# MTB-v1_2_0.net
KiCad netlist of a schematic drawn in EAGLE
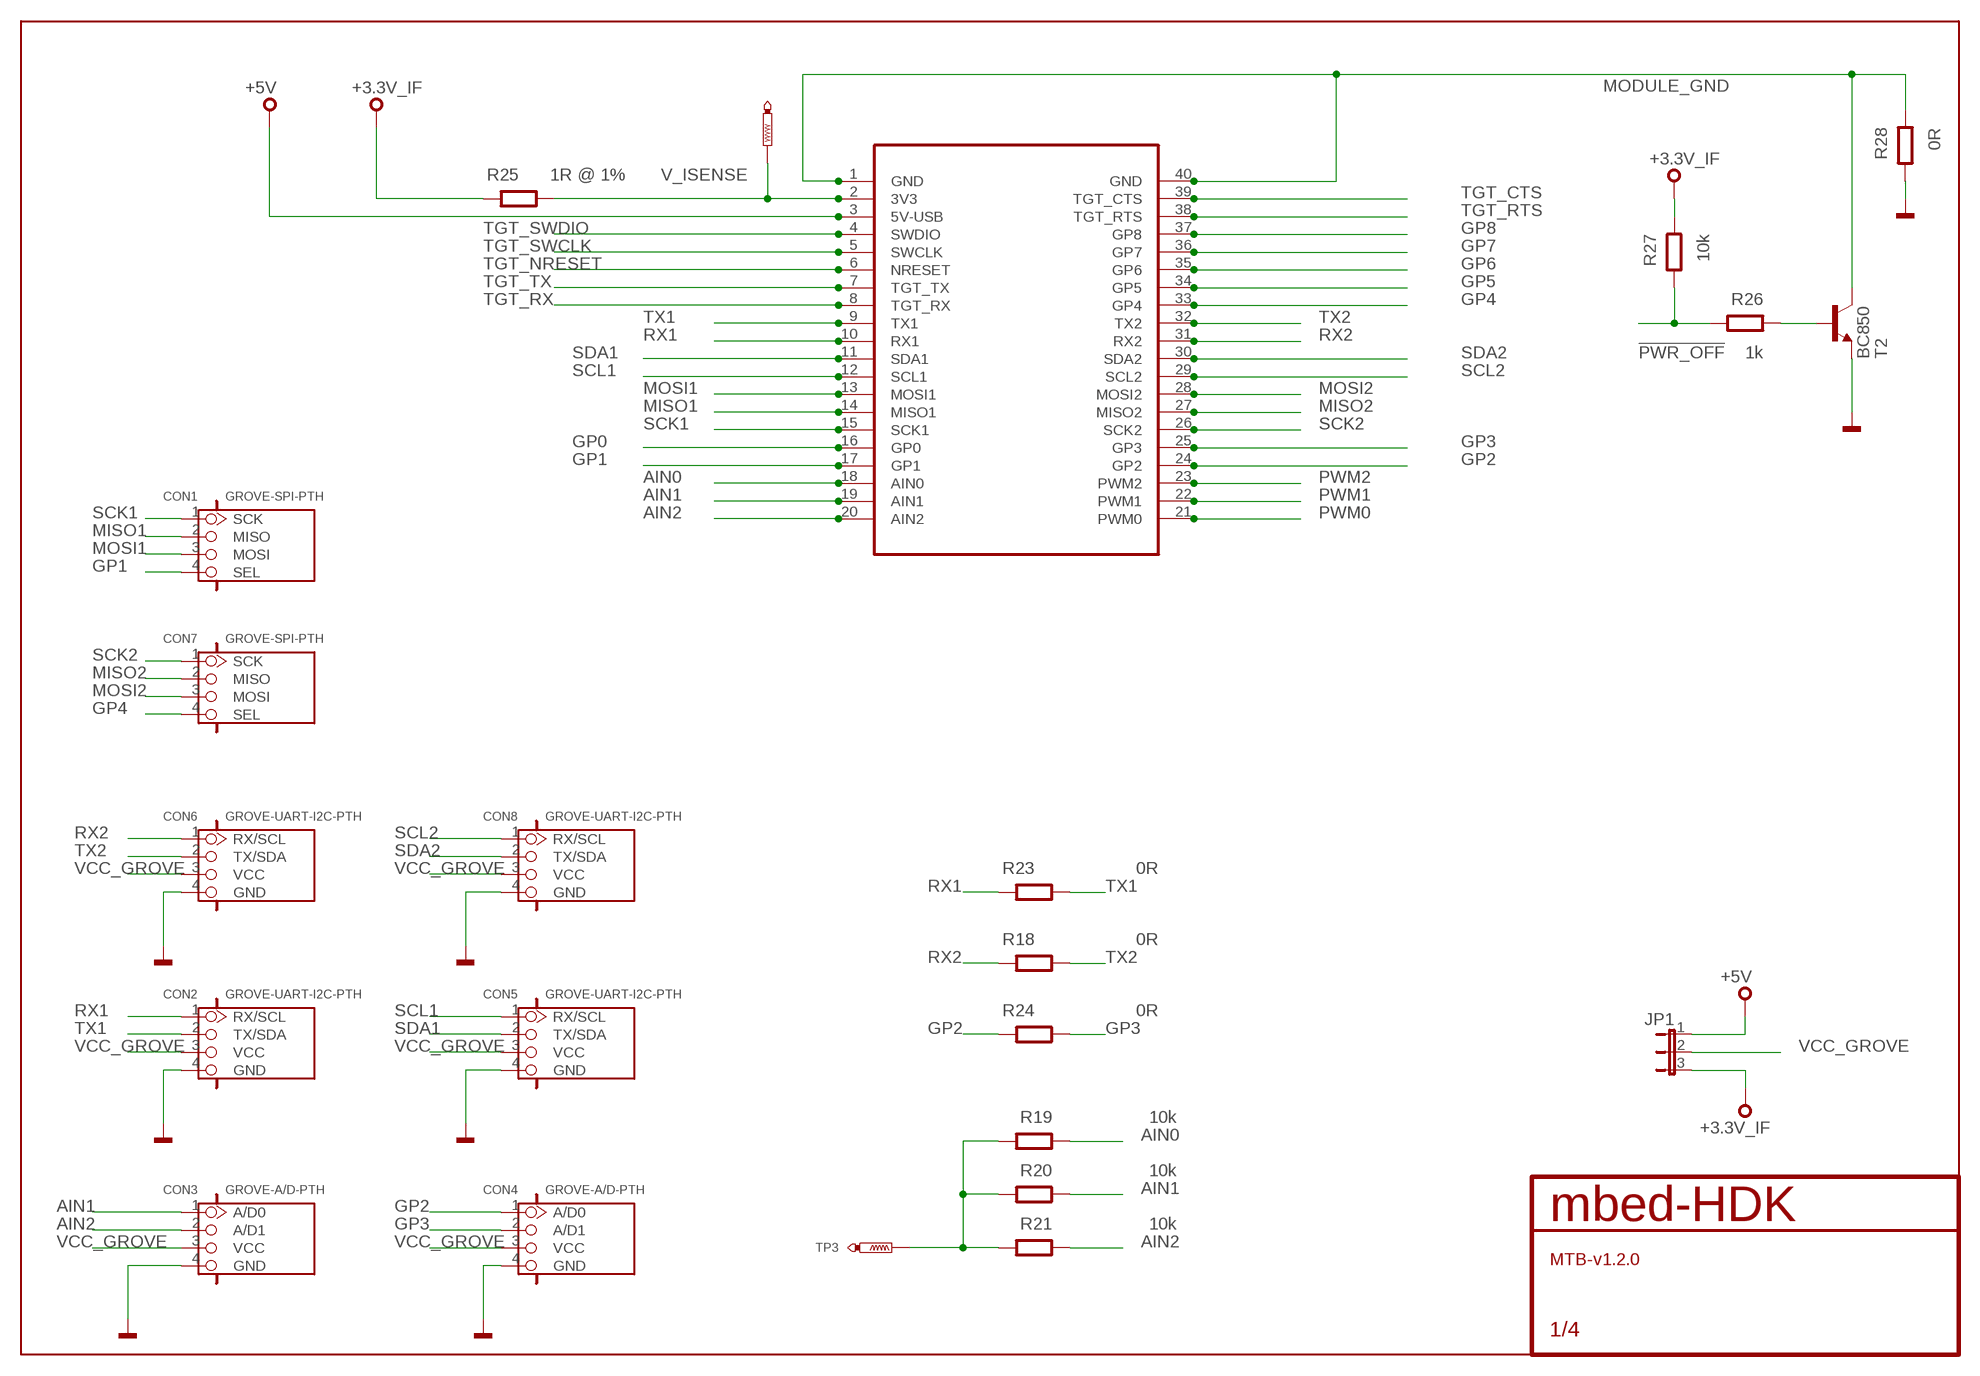
[diagram p0: schematic, sheet 1]
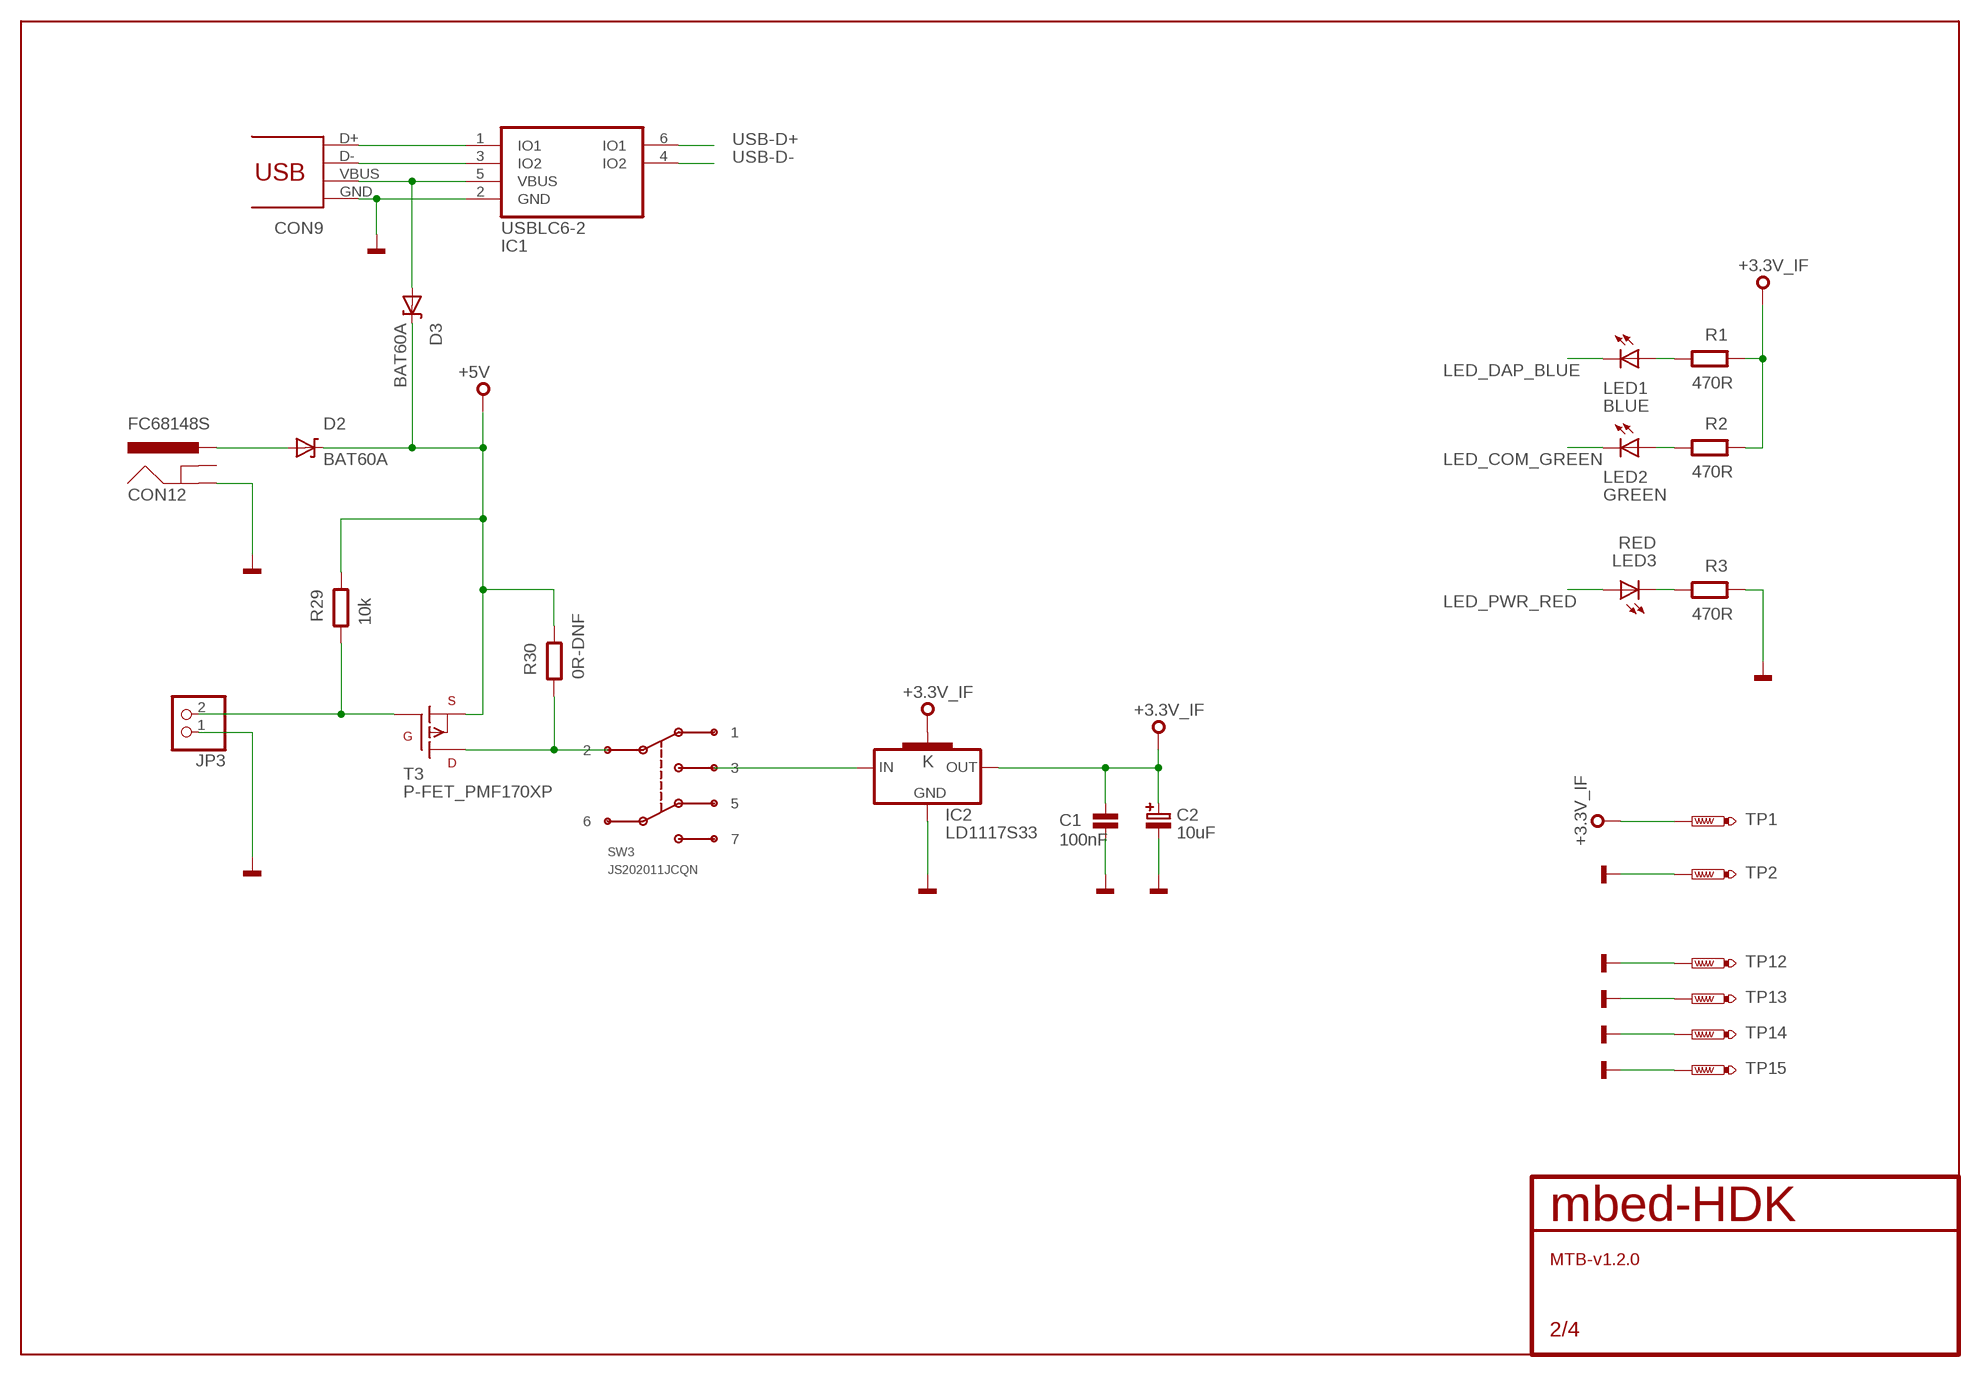
[diagram p1: schematic, sheet 2]
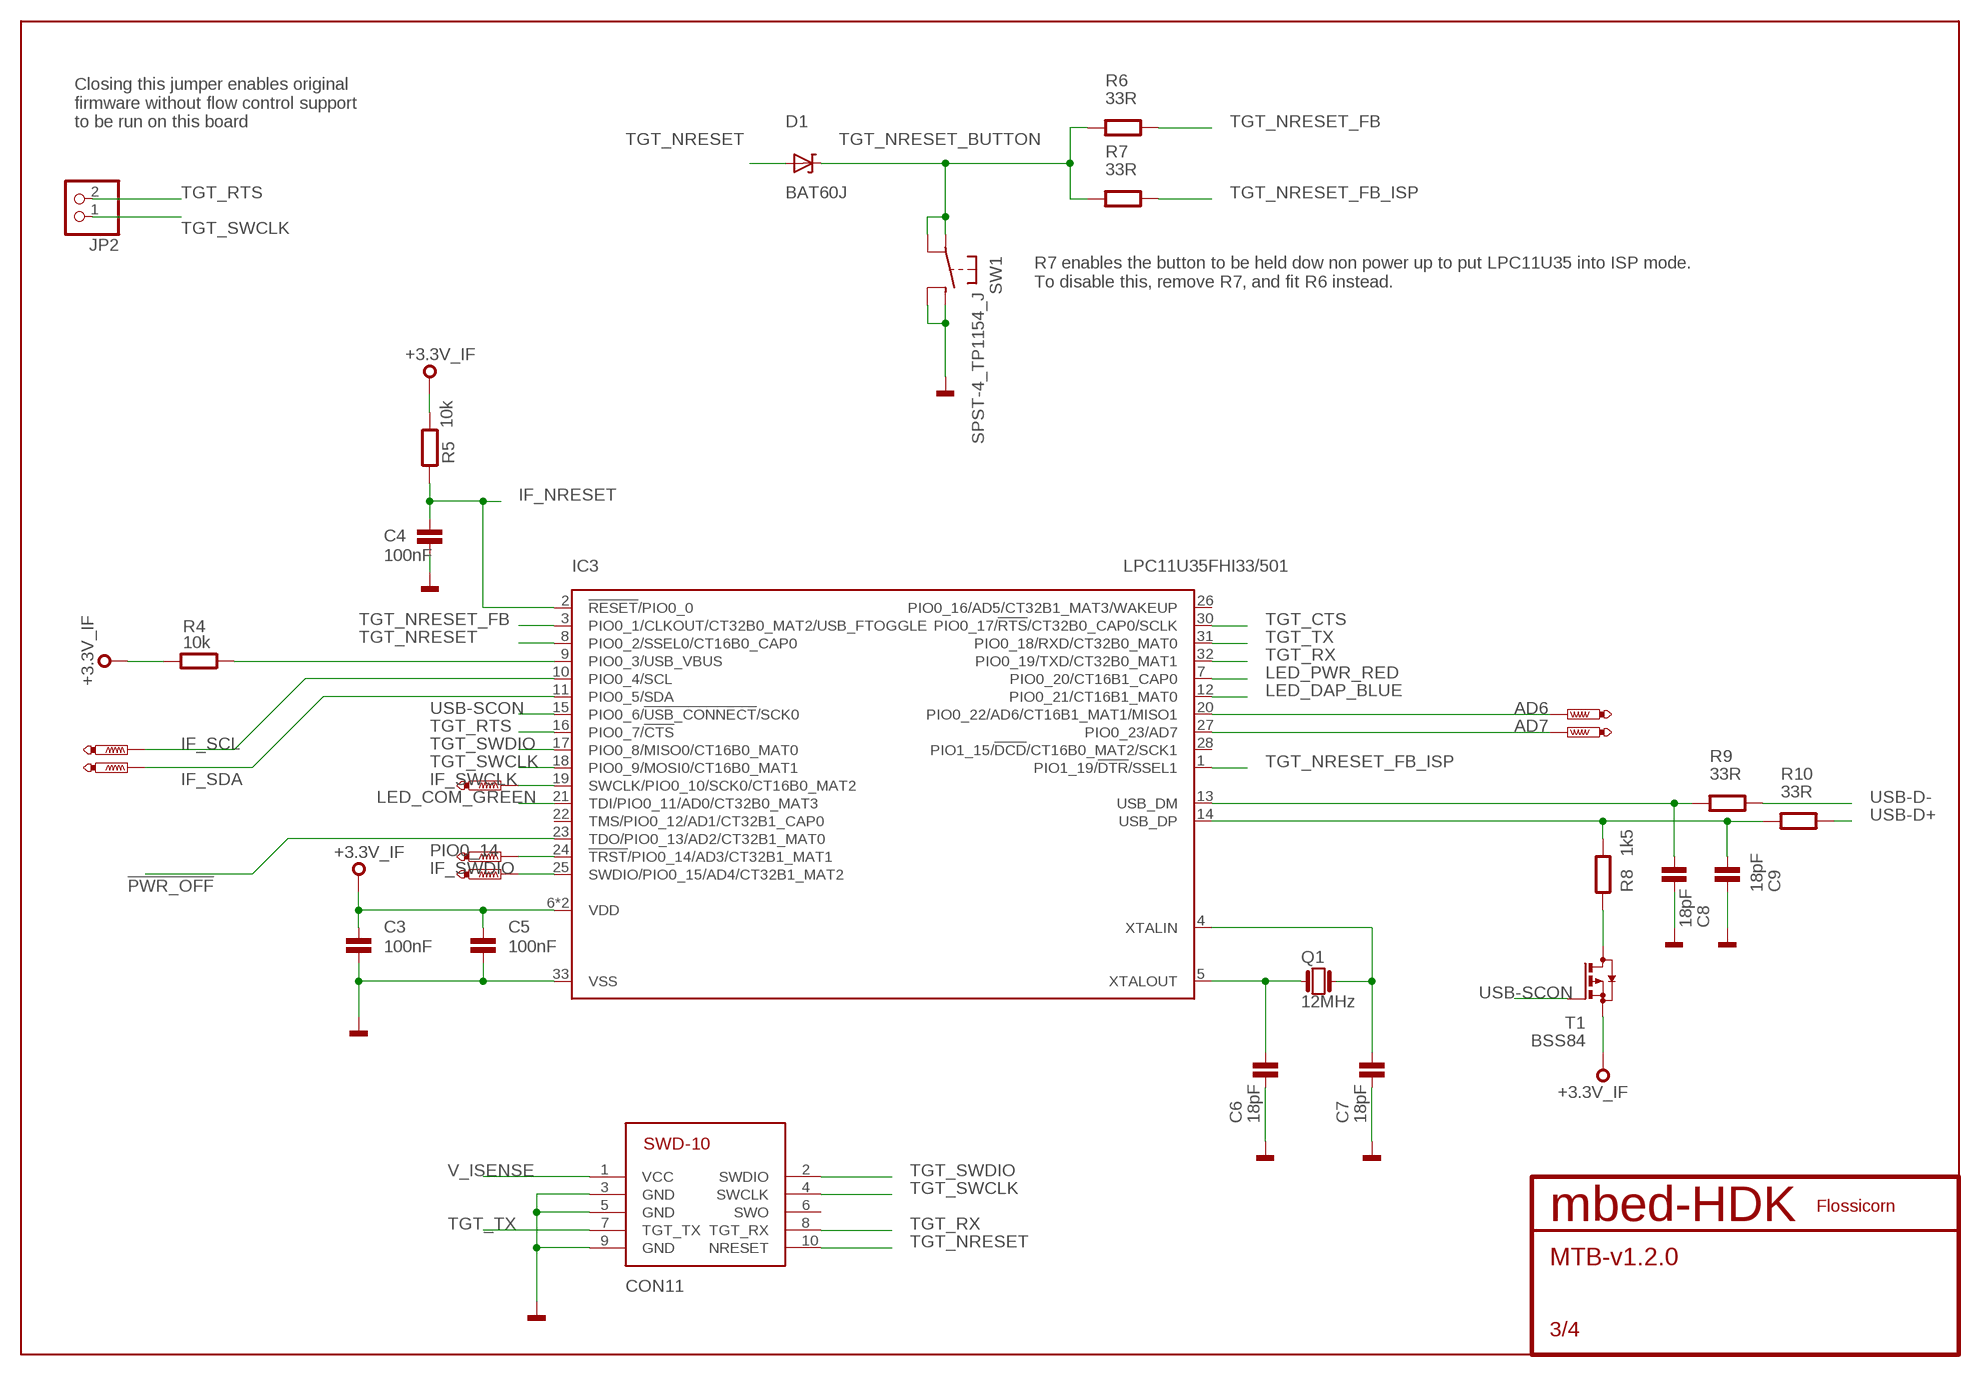
[diagram p2: schematic, sheet 3]
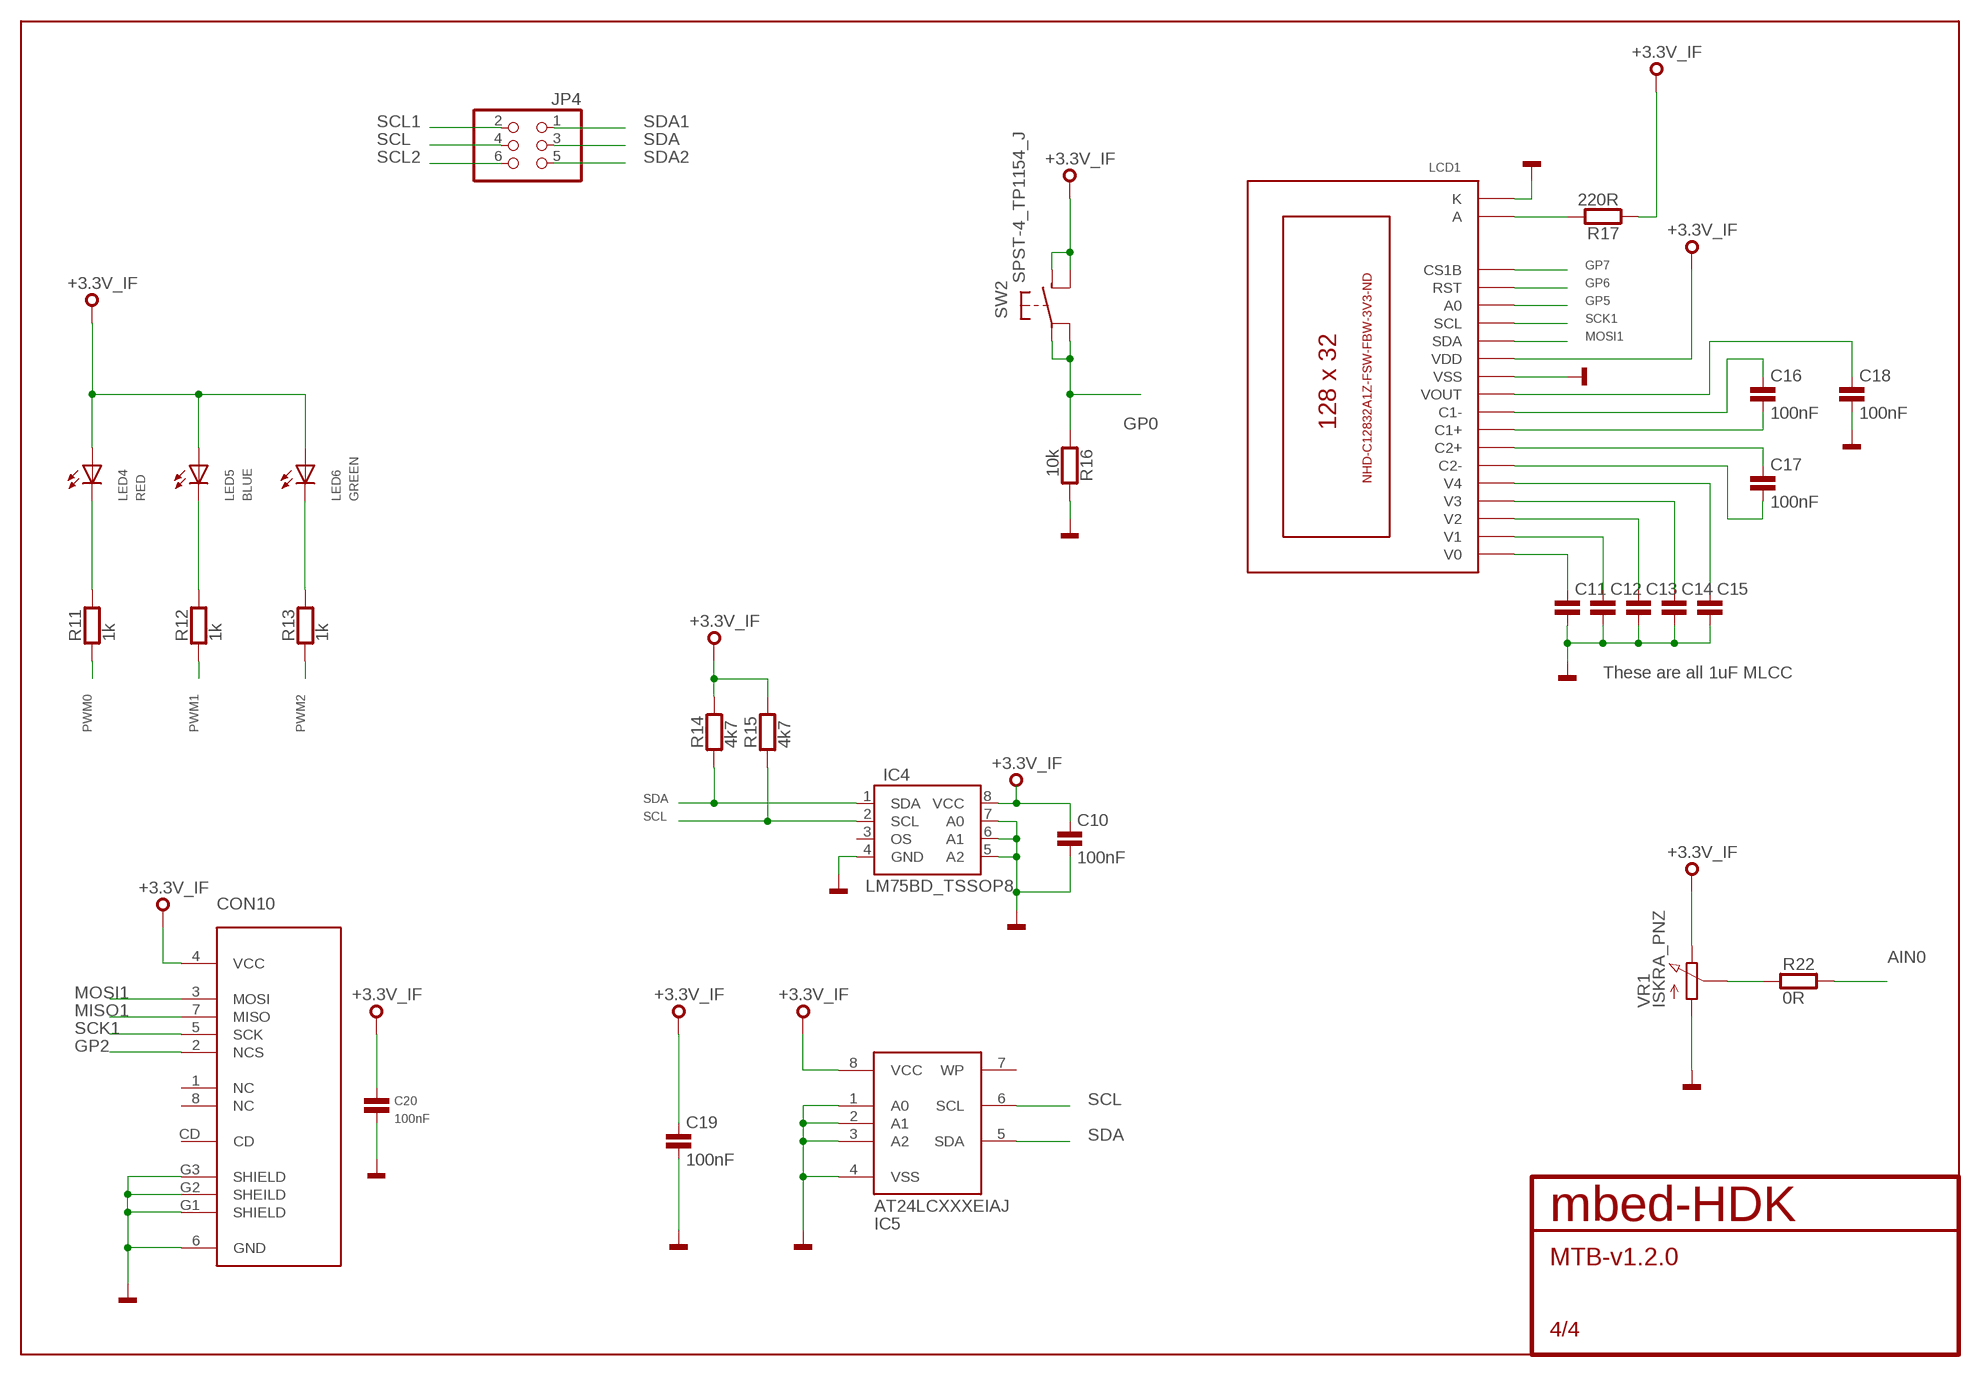
[diagram p3: schematic, sheet 4]

(export (version "E")
  (design (tool "Eeschema 10.0.6"))
  (components
    (comp (ref "C1")
      (value "100nF")
      (footprint "eagle-import:0603")
      (libsource (lib "eagle-import") (part "C0603"))
    )
    (comp (ref "C2")
      (value "10uF")
      (footprint "eagle-import:SMC_B")
      (libsource (lib "eagle-import") (part "C-POLB"))
    )
    (comp (ref "CON9")
      (value "USB_MICROB")
      (footprint "eagle-import:MOLEX-47364-0001")
      (libsource (lib "eagle-import") (part "USB_MICROB"))
    )
    (comp (ref "CON12")
      (value "FC68148S")
      (footprint "eagle-import:FC68148S")
      (libsource (lib "eagle-import") (part "FC68148S"))
    )
    (comp (ref "D2")
      (value "BAT60A")
      (footprint "eagle-import:SOD323")
      (fields (field (name "MF") "Infineon"))
      (libsource (lib "eagle-import") (part "mbed-HDK-Transistor_BAT60A"))
    )
    (comp (ref "D3")
      (value "BAT60A")
      (footprint "eagle-import:SOD323")
      (fields (field (name "MF") "Infineon"))
      (libsource (lib "eagle-import") (part "mbed-HDK-Transistor_BAT60A"))
    )
    (comp (ref "IC1")
      (value "USBLC6-2SC6")
      (footprint "eagle-import:SOT23-6L")
      (libsource (lib "eagle-import") (part "USBLC6-2SC6"))
    )
    (comp (ref "IC2")
      (value "LD1117S33")
      (footprint "eagle-import:SOT223")
      (libsource (lib "eagle-import") (part "LD1117S33"))
    )
    (comp (ref "JP3")
      (value "PINHD-1X2")
      (footprint "eagle-import:1X02")
      (libsource (lib "eagle-import") (part "PINHD-1X2"))
    )
    (comp (ref "LED1")
      (value "BLUE")
      (footprint "eagle-import:CHIPLED_0603")
      (libsource (lib "eagle-import") (part "LED0603"))
    )
    (comp (ref "LED2")
      (value "GREEN")
      (footprint "eagle-import:CHIPLED_0603")
      (libsource (lib "eagle-import") (part "LED0603"))
    )
    (comp (ref "LED3")
      (value "RED")
      (footprint "eagle-import:CHIPLED_0603")
      (libsource (lib "eagle-import") (part "LED0603"))
    )
    (comp (ref "R1")
      (value "470R")
      (footprint "eagle-import:0603@1")
      (libsource (lib "eagle-import") (part "R0603"))
    )
    (comp (ref "R2")
      (value "470R")
      (footprint "eagle-import:0603@1")
      (libsource (lib "eagle-import") (part "R0603"))
    )
    (comp (ref "R3")
      (value "470R")
      (footprint "eagle-import:0603@1")
      (libsource (lib "eagle-import") (part "R0603"))
    )
    (comp (ref "R29")
      (value "10k")
      (footprint "eagle-import:0603@1")
      (libsource (lib "eagle-import") (part "R0603"))
    )
    (comp (ref "R30")
      (value "0R-DNF")
      (footprint "eagle-import:0603@1")
      (libsource (lib "eagle-import") (part "R0603"))
    )
    (comp (ref "SW3")
      (value "JS202011JCQN")
      (footprint "eagle-import:JS202011JCQN")
      (fields (field (name "MF") "C&K Components"))
      (libsource (lib "eagle-import") (part "JS202011JCQN"))
    )
    (comp (ref "T3")
      (value "P-FET_PMF170XP")
      (footprint "eagle-import:SOT23-BEC")
      (libsource (lib "eagle-import") (part "P-FET_PMF170XP"))
    )
    (comp (ref "TP1")
      (value "TEST-POINT-50R-PTH")
      (footprint "eagle-import:TP50-PTH")
      (libsource (lib "eagle-import") (part "TEST-POINT-50R-PTH"))
    )
    (comp (ref "TP2")
      (value "TEST-POINT-50R-PTH")
      (footprint "eagle-import:TP50-PTH")
      (libsource (lib "eagle-import") (part "TEST-POINT-50R-PTH"))
    )
    (comp (ref "TP12")
      (value "TEST-POINT-50R-PTH")
      (footprint "eagle-import:TP50-PTH")
      (libsource (lib "eagle-import") (part "TEST-POINT-50R-PTH"))
    )
    (comp (ref "TP13")
      (value "TEST-POINT-50R-PTH")
      (footprint "eagle-import:TP50-PTH")
      (libsource (lib "eagle-import") (part "TEST-POINT-50R-PTH"))
    )
    (comp (ref "TP14")
      (value "TEST-POINT-50R-PTH")
      (footprint "eagle-import:TP50-PTH")
      (libsource (lib "eagle-import") (part "TEST-POINT-50R-PTH"))
    )
    (comp (ref "TP15")
      (value "TEST-POINT-50R-PTH")
      (footprint "eagle-import:TP50-PTH")
      (libsource (lib "eagle-import") (part "TEST-POINT-50R-PTH"))
    )
    (comp (ref "C10")
      (value "100nF")
      (footprint "eagle-import:0603")
      (libsource (lib "eagle-import") (part "mbed-rlcq_C0603"))
    )
    (comp (ref "C11")
      (value "100nF")
      (footprint "eagle-import:0603")
      (libsource (lib "eagle-import") (part "mbed-rlcq_C0603"))
    )
    (comp (ref "C12")
      (value "100nF")
      (footprint "eagle-import:0603")
      (libsource (lib "eagle-import") (part "mbed-rlcq_C0603"))
    )
    (comp (ref "C13")
      (value "100nF")
      (footprint "eagle-import:0603")
      (libsource (lib "eagle-import") (part "mbed-rlcq_C0603"))
    )
    (comp (ref "C14")
      (value "100nF")
      (footprint "eagle-import:0603")
      (libsource (lib "eagle-import") (part "mbed-rlcq_C0603"))
    )
    (comp (ref "C15")
      (value "100nF")
      (footprint "eagle-import:0603")
      (libsource (lib "eagle-import") (part "mbed-rlcq_C0603"))
    )
    (comp (ref "C16")
      (value "100nF")
      (footprint "eagle-import:0603")
      (libsource (lib "eagle-import") (part "mbed-rlcq_C0603"))
    )
    (comp (ref "C17")
      (value "100nF")
      (footprint "eagle-import:0603")
      (libsource (lib "eagle-import") (part "mbed-rlcq_C0603"))
    )
    (comp (ref "C18")
      (value "100nF")
      (footprint "eagle-import:0603")
      (libsource (lib "eagle-import") (part "mbed-rlcq_C0603"))
    )
    (comp (ref "C19")
      (value "100nF")
      (footprint "eagle-import:0603")
      (libsource (lib "eagle-import") (part "mbed-rlcq_C0603"))
    )
    (comp (ref "C20")
      (value "100nF")
      (footprint "eagle-import:0603")
      (libsource (lib "eagle-import") (part "C0603"))
    )
    (comp (ref "CON10")
      (value "MICRO-SD")
      (footprint "eagle-import:AMPHENOL-101-00660-68-6")
      (libsource (lib "eagle-import") (part "MICRO-SD"))
    )
    (comp (ref "IC4")
      (value "LM75BD_TSSOP8")
      (footprint "eagle-import:TSSOP8")
      (libsource (lib "eagle-import") (part "LM75BD_TSSOP8"))
    )
    (comp (ref "IC5")
      (value "AT24LCXXXEIAJ")
      (footprint "eagle-import:SO08-EIAJ")
      (libsource (lib "eagle-import") (part "AT24LCXXXEIAJ"))
    )
    (comp (ref "JP4")
      (value "PINHD-2X3")
      (footprint "eagle-import:2X03")
      (libsource (lib "eagle-import") (part "PINHD-2X3"))
    )
    (comp (ref "LCD1")
      (value "C12832A1Z")
      (footprint "eagle-import:C12832A1Z")
      (libsource (lib "eagle-import") (part "C12832A1Z"))
    )
    (comp (ref "LED4")
      (value "RED")
      (footprint "eagle-import:CHIPLED_0603")
      (libsource (lib "eagle-import") (part "LED0603"))
    )
    (comp (ref "LED5")
      (value "BLUE")
      (footprint "eagle-import:CHIPLED_0603")
      (libsource (lib "eagle-import") (part "LED0603"))
    )
    (comp (ref "LED6")
      (value "GREEN")
      (footprint "eagle-import:CHIPLED_0603")
      (libsource (lib "eagle-import") (part "LED0603"))
    )
    (comp (ref "R11")
      (value "1k")
      (footprint "eagle-import:0603")
      (libsource (lib "eagle-import") (part "mbed-rlcq_R0603"))
    )
    (comp (ref "R12")
      (value "1k")
      (footprint "eagle-import:0603")
      (libsource (lib "eagle-import") (part "mbed-rlcq_R0603"))
    )
    (comp (ref "R13")
      (value "1k")
      (footprint "eagle-import:0603")
      (libsource (lib "eagle-import") (part "mbed-rlcq_R0603"))
    )
    (comp (ref "R14")
      (value "4k7")
      (footprint "eagle-import:0603")
      (libsource (lib "eagle-import") (part "mbed-rlcq_R0603"))
    )
    (comp (ref "R15")
      (value "4k7")
      (footprint "eagle-import:0603")
      (libsource (lib "eagle-import") (part "mbed-rlcq_R0603"))
    )
    (comp (ref "R16")
      (value "10k")
      (footprint "eagle-import:0603")
      (libsource (lib "eagle-import") (part "mbed-rlcq_R0603"))
    )
    (comp (ref "R17")
      (value "220R")
      (footprint "eagle-import:0603")
      (libsource (lib "eagle-import") (part "mbed-rlcq_R0603"))
    )
    (comp (ref "R22")
      (value "0R")
      (footprint "eagle-import:0603")
      (libsource (lib "eagle-import") (part "mbed-rlcq_R0603"))
    )
    (comp (ref "SW2")
      (value "SPST-4_TP1154_J")
      (footprint "eagle-import:TP-1154X")
      (libsource (lib "eagle-import") (part "SPST-4_TP1154_J"))
    )
    (comp (ref "VR1")
      (value "ISKRA_PNZ")
      (footprint "eagle-import:CA14V")
      (libsource (lib "eagle-import") (part "ISKRA_PNZ"))
    )
    (comp (ref "CON1")
      (value "GROVE-SPI-PTH")
      (footprint "eagle-import:HW4-2.0")
      (libsource (lib "eagle-import") (part "GROVE-SPI-PTH"))
    )
    (comp (ref "CON2")
      (value "GROVE-UART-I2C-PTH")
      (footprint "eagle-import:HW4-2.0")
      (libsource (lib "eagle-import") (part "GROVE-UART-I2C-PTH"))
    )
    (comp (ref "CON3")
      (value "GROVE-A/D-PTH")
      (footprint "eagle-import:HW4-2.0")
      (libsource (lib "eagle-import") (part "GROVE-A/D-PTH"))
    )
    (comp (ref "CON4")
      (value "GROVE-A/D-PTH")
      (footprint "eagle-import:HW4-2.0")
      (libsource (lib "eagle-import") (part "GROVE-A/D-PTH"))
    )
    (comp (ref "CON5")
      (value "GROVE-UART-I2C-PTH")
      (footprint "eagle-import:HW4-2.0")
      (libsource (lib "eagle-import") (part "GROVE-UART-I2C-PTH"))
    )
    (comp (ref "CON6")
      (value "GROVE-UART-I2C-PTH")
      (footprint "eagle-import:HW4-2.0")
      (libsource (lib "eagle-import") (part "GROVE-UART-I2C-PTH"))
    )
    (comp (ref "CON7")
      (value "GROVE-SPI-PTH")
      (footprint "eagle-import:HW4-2.0")
      (libsource (lib "eagle-import") (part "GROVE-SPI-PTH"))
    )
    (comp (ref "CON8")
      (value "GROVE-UART-I2C-PTH")
      (footprint "eagle-import:HW4-2.0")
      (libsource (lib "eagle-import") (part "GROVE-UART-I2C-PTH"))
    )
    (comp (ref "JP1")
      (value "JP2E")
      (footprint "eagle-import:JP2")
      (libsource (lib "eagle-import") (part "JP2E"))
    )
    (comp (ref "R18")
      (value "0R")
      (footprint "eagle-import:0603@1")
      (libsource (lib "eagle-import") (part "R0603"))
    )
    (comp (ref "R19")
      (value "10k")
      (footprint "eagle-import:0603@1")
      (libsource (lib "eagle-import") (part "R0603"))
    )
    (comp (ref "R20")
      (value "10k")
      (footprint "eagle-import:0603@1")
      (libsource (lib "eagle-import") (part "R0603"))
    )
    (comp (ref "R21")
      (value "10k")
      (footprint "eagle-import:0603@1")
      (libsource (lib "eagle-import") (part "R0603"))
    )
    (comp (ref "R23")
      (value "0R")
      (footprint "eagle-import:0603@1")
      (libsource (lib "eagle-import") (part "R0603"))
    )
    (comp (ref "R24")
      (value "0R")
      (footprint "eagle-import:0603@1")
      (libsource (lib "eagle-import") (part "R0603"))
    )
    (comp (ref "R25")
      (value "1R @ 1%")
      (footprint "eagle-import:0603@1")
      (libsource (lib "eagle-import") (part "R0603"))
    )
    (comp (ref "R26")
      (value "1k")
      (footprint "eagle-import:0603@1")
      (libsource (lib "eagle-import") (part "R0603"))
    )
    (comp (ref "R27")
      (value "10k")
      (footprint "eagle-import:0603@1")
      (libsource (lib "eagle-import") (part "R0603"))
    )
    (comp (ref "R28")
      (value "0R")
      (footprint "eagle-import:0603@1")
      (libsource (lib "eagle-import") (part "R0603"))
    )
    (comp (ref "SKT1")
      (value "MODULE_SOCKET")
      (footprint "eagle-import:MODULE_SOCKET")
      (libsource (lib "eagle-import") (part "MODULE_SOCKET"))
    )
    (comp (ref "T2")
      (value "BC850")
      (footprint "eagle-import:SOT23")
      (libsource (lib "eagle-import") (part "BC850"))
    )
    (comp (ref "TP3")
      (value "TEST-POINT-50R-PTH")
      (footprint "eagle-import:TP50-PTH")
      (libsource (lib "eagle-import") (part "TEST-POINT-50R-PTH"))
    )
    (comp (ref "TP8")
      (value "PTR1TP07R")
      (footprint "eagle-import:TP07R")
      (libsource (lib "eagle-import") (part "PTR1TP07R"))
    )
    (comp (ref "C3")
      (value "100nF")
      (footprint "eagle-import:0603")
      (libsource (lib "eagle-import") (part "C0603"))
    )
    (comp (ref "C4")
      (value "100nF")
      (footprint "eagle-import:0603")
      (libsource (lib "eagle-import") (part "C0603"))
    )
    (comp (ref "C5")
      (value "100nF")
      (footprint "eagle-import:0603")
      (libsource (lib "eagle-import") (part "C0603"))
    )
    (comp (ref "C6")
      (value "18pF")
      (footprint "eagle-import:0603")
      (libsource (lib "eagle-import") (part "C0603"))
    )
    (comp (ref "C7")
      (value "18pF")
      (footprint "eagle-import:0603")
      (libsource (lib "eagle-import") (part "C0603"))
    )
    (comp (ref "C8")
      (value "18pF")
      (footprint "eagle-import:0603")
      (libsource (lib "eagle-import") (part "C0603"))
    )
    (comp (ref "C9")
      (value "18pF")
      (footprint "eagle-import:0603")
      (libsource (lib "eagle-import") (part "C0603"))
    )
    (comp (ref "CON11")
      (value "SWD-10/TC2050_SMD")
      (footprint "eagle-import:FTSH-105-02")
      (libsource (lib "eagle-import") (part "SWD-10/TC2050_SMD"))
    )
    (comp (ref "D1")
      (value "BAT60J")
      (footprint "eagle-import:BAT60A")
      (libsource (lib "eagle-import") (part "BAT60A"))
    )
    (comp (ref "IC3")
      (value "LPC11U35FHI33/501")
      (footprint "eagle-import:SOT617-3")
      (libsource (lib "eagle-import") (part "LPC11U35FHI33/501"))
    )
    (comp (ref "JP2")
      (value "PINHD-1X2")
      (footprint "eagle-import:1X02")
      (libsource (lib "eagle-import") (part "PINHD-1X2"))
    )
    (comp (ref "Q1")
      (value "12MHz")
      (footprint "eagle-import:3.2X.2.5")
      (libsource (lib "eagle-import") (part "Q_3.2X2.5"))
    )
    (comp (ref "R4")
      (value "10k")
      (footprint "eagle-import:0603@1")
      (libsource (lib "eagle-import") (part "R0603"))
    )
    (comp (ref "R5")
      (value "10k")
      (footprint "eagle-import:0603@1")
      (libsource (lib "eagle-import") (part "R0603"))
    )
    (comp (ref "R6")
      (value "33R")
      (footprint "eagle-import:0603@1")
      (libsource (lib "eagle-import") (part "R0603"))
    )
    (comp (ref "R7")
      (value "33R")
      (footprint "eagle-import:0603@1")
      (libsource (lib "eagle-import") (part "R0603"))
    )
    (comp (ref "R8")
      (value "1k5")
      (footprint "eagle-import:0603@1")
      (libsource (lib "eagle-import") (part "R0603"))
    )
    (comp (ref "R9")
      (value "33R")
      (footprint "eagle-import:0603@1")
      (libsource (lib "eagle-import") (part "R0603"))
    )
    (comp (ref "R10")
      (value "33R")
      (footprint "eagle-import:0603@1")
      (libsource (lib "eagle-import") (part "R0603"))
    )
    (comp (ref "SS1")
      (value "FLOSSICORN0.5")
      (footprint "eagle-import:FLOSSICORN-0.5")
      (libsource (lib "eagle-import") (part "FLOSSICORN0.5"))
    )
    (comp (ref "SW1")
      (value "SPST-4_TP1154_J")
      (footprint "eagle-import:TP-1154X")
      (libsource (lib "eagle-import") (part "SPST-4_TP1154_J"))
    )
    (comp (ref "T1")
      (value "BSS84")
      (footprint "eagle-import:SOT23")
      (libsource (lib "eagle-import") (part "BSS84"))
    )
    (comp (ref "TP4")
      (value "PTR1TP07R")
      (footprint "eagle-import:TP07R")
      (libsource (lib "eagle-import") (part "PTR1TP07R"))
    )
    (comp (ref "TP5")
      (value "PTR1TP07R")
      (footprint "eagle-import:TP07R")
      (libsource (lib "eagle-import") (part "PTR1TP07R"))
    )
    (comp (ref "TP6")
      (value "PTR1TP07R")
      (footprint "eagle-import:TP07R")
      (libsource (lib "eagle-import") (part "PTR1TP07R"))
    )
    (comp (ref "TP7")
      (value "PTR1TP07R")
      (footprint "eagle-import:TP07R")
      (libsource (lib "eagle-import") (part "PTR1TP07R"))
    )
    (comp (ref "TP9")
      (value "PTR1TP07R")
      (footprint "eagle-import:TP07R")
      (libsource (lib "eagle-import") (part "PTR1TP07R"))
    )
    (comp (ref "TP10")
      (value "PTR1TP07R")
      (footprint "eagle-import:TP07R")
      (libsource (lib "eagle-import") (part "PTR1TP07R"))
    )
    (comp (ref "TP11")
      (value "PTR1TP07R")
      (footprint "eagle-import:TP07R")
      (libsource (lib "eagle-import") (part "PTR1TP07R"))
    )
  )
  (nets
    (net (code "1") (name "+3.3V_IF") (class "Default")
      (node (ref "C1") (pin "1") (pinfunction "P$1_1") (pintype "passive"))
      (node (ref "C10") (pin "1") (pinfunction "P$1_1") (pintype "passive"))
      (node (ref "C19") (pin "1") (pinfunction "P$1_1") (pintype "passive"))
      (node (ref "C2") (pin "+") (pinfunction "+_+") (pintype "passive"))
      (node (ref "C20") (pin "1") (pinfunction "P$1_1") (pintype "passive"))
      (node (ref "C3") (pin "1") (pinfunction "P$1_1") (pintype "passive"))
      (node (ref "C5") (pin "1") (pinfunction "P$1_1") (pintype "passive"))
      (node (ref "CON10") (pin "4") (pinfunction "VCC_4") (pintype "bidirectional"))
      (node (ref "IC2") (pin "2") (pinfunction "OUT_2") (pintype "passive"))
      (node (ref "IC2") (pin "4") (pinfunction "K_4") (pintype "passive"))
      (node (ref "IC3") (pin "29") (pinfunction "VDD_29") (pintype "passive"))
      (node (ref "IC3") (pin "6") (pinfunction "VDD_6") (pintype "passive"))
      (node (ref "IC4") (pin "8") (pinfunction "VCC_8") (pintype "bidirectional"))
      (node (ref "IC5") (pin "8") (pinfunction "VCC_8") (pintype "power_in"))
      (node (ref "JP1") (pin "3") (pinfunction "3_3") (pintype "passive"))
      (node (ref "LCD1") (pin "P$12") (pinfunction "VDD_P$12") (pintype "bidirectional"))
      (node (ref "LED4") (pin "A") (pinfunction "A_A") (pintype "passive"))
      (node (ref "LED5") (pin "A") (pinfunction "A_A") (pintype "passive"))
      (node (ref "LED6") (pin "A") (pinfunction "A_A") (pintype "passive"))
      (node (ref "R1") (pin "1") (pinfunction "P$1_1") (pintype "passive"))
      (node (ref "R14") (pin "2") (pinfunction "P$2_2") (pintype "passive"))
      (node (ref "R15") (pin "2") (pinfunction "P$2_2") (pintype "passive"))
      (node (ref "R17") (pin "1") (pinfunction "P$1_1") (pintype "passive"))
      (node (ref "R2") (pin "1") (pinfunction "P$1_1") (pintype "passive"))
      (node (ref "R25") (pin "2") (pinfunction "P$2_2") (pintype "passive"))
      (node (ref "R27") (pin "1") (pinfunction "P$1_1") (pintype "passive"))
      (node (ref "R4") (pin "2") (pinfunction "P$2_2") (pintype "passive"))
      (node (ref "R5") (pin "2") (pinfunction "P$2_2") (pintype "passive"))
      (node (ref "SW2") (pin "B1") (pinfunction "B1_B1") (pintype "passive"))
      (node (ref "SW2") (pin "B2") (pinfunction "B2_B2") (pintype "passive"))
      (node (ref "T1") (pin "2") (pinfunction "S_2") (pintype "passive"))
      (node (ref "TP1") (pin "TP") (pinfunction "TP_TP") (pintype "input"))
      (node (ref "VR1") (pin "P$3") (pinfunction "E_P$3") (pintype "passive"))
    )
    (net (code "2") (name "+5V") (class "Default")
      (node (ref "D2") (pin "K") (pinfunction "K_K") (pintype "passive"))
      (node (ref "D3") (pin "K") (pinfunction "K_K") (pintype "passive"))
      (node (ref "JP1") (pin "1") (pinfunction "1_1") (pintype "passive"))
      (node (ref "R29") (pin "1") (pinfunction "P$1_1") (pintype "passive"))
      (node (ref "R30") (pin "1") (pinfunction "P$1_1") (pintype "passive"))
      (node (ref "SKT1") (pin "3") (pinfunction "5V-USB_3") (pintype "bidirectional"))
      (node (ref "SKT1") (pin "P$43") (pinfunction "P$43_P$43") (pintype "bidirectional"))
      (node (ref "T3") (pin "E") (pinfunction "S_E") (pintype "passive"))
    )
    (net (code "3") (name "AD6") (class "Default")
      (node (ref "IC3") (pin "20") (pinfunction "PIO0_22/AD6/CT16B1_MAT1/MISO1_20") (pintype "bidirectional"))
      (node (ref "TP7") (pin "TP") (pinfunction "TP_TP") (pintype "input"))
    )
    (net (code "4") (name "AD7") (class "Default")
      (node (ref "IC3") (pin "27") (pinfunction "PIO0_23/AD7_27") (pintype "bidirectional"))
      (node (ref "TP6") (pin "TP") (pinfunction "TP_TP") (pintype "input"))
    )
    (net (code "5") (name "AIN0") (class "Default")
      (node (ref "R19") (pin "1") (pinfunction "P$1_1") (pintype "passive"))
      (node (ref "R22") (pin "2") (pinfunction "P$2_2") (pintype "passive"))
      (node (ref "SKT1") (pin "18") (pinfunction "AIN0_18") (pintype "bidirectional"))
      (node (ref "SKT1") (pin "P$58") (pinfunction "P$58_P$58") (pintype "bidirectional"))
    )
    (net (code "6") (name "AIN1") (class "Default")
      (node (ref "CON3") (pin "1") (pinfunction "A/D0_1") (pintype "bidirectional"))
      (node (ref "R20") (pin "1") (pinfunction "P$1_1") (pintype "passive"))
      (node (ref "SKT1") (pin "19") (pinfunction "AIN1_19") (pintype "bidirectional"))
      (node (ref "SKT1") (pin "P$59") (pinfunction "P$59_P$59") (pintype "bidirectional"))
    )
    (net (code "7") (name "AIN2") (class "Default")
      (node (ref "CON3") (pin "2") (pinfunction "A/D1_2") (pintype "bidirectional"))
      (node (ref "R21") (pin "1") (pinfunction "P$1_1") (pintype "passive"))
      (node (ref "SKT1") (pin "20") (pinfunction "AIN2_20") (pintype "bidirectional"))
      (node (ref "SKT1") (pin "P$60") (pinfunction "P$60_P$60") (pintype "bidirectional"))
    )
    (net (code "8") (name "GND") (class "Default")
      (node (ref "C1") (pin "2") (pinfunction "P$2_2") (pintype "passive"))
      (node (ref "C10") (pin "2") (pinfunction "P$2_2") (pintype "passive"))
      (node (ref "C11") (pin "2") (pinfunction "P$2_2") (pintype "passive"))
      (node (ref "C12") (pin "2") (pinfunction "P$2_2") (pintype "passive"))
      (node (ref "C13") (pin "2") (pinfunction "P$2_2") (pintype "passive"))
      (node (ref "C14") (pin "2") (pinfunction "P$2_2") (pintype "passive"))
      (node (ref "C15") (pin "2") (pinfunction "P$2_2") (pintype "passive"))
      (node (ref "C18") (pin "2") (pinfunction "P$2_2") (pintype "passive"))
      (node (ref "C19") (pin "2") (pinfunction "P$2_2") (pintype "passive"))
      (node (ref "C2") (pin "-") (pinfunction "-_-") (pintype "passive"))
      (node (ref "C20") (pin "2") (pinfunction "P$2_2") (pintype "passive"))
      (node (ref "C3") (pin "2") (pinfunction "P$2_2") (pintype "passive"))
      (node (ref "C4") (pin "2") (pinfunction "P$2_2") (pintype "passive"))
      (node (ref "C5") (pin "2") (pinfunction "P$2_2") (pintype "passive"))
      (node (ref "C6") (pin "2") (pinfunction "P$2_2") (pintype "passive"))
      (node (ref "C7") (pin "2") (pinfunction "P$2_2") (pintype "passive"))
      (node (ref "C8") (pin "2") (pinfunction "P$2_2") (pintype "passive"))
      (node (ref "C9") (pin "2") (pinfunction "P$2_2") (pintype "passive"))
      (node (ref "CON10") (pin "6") (pinfunction "GND_6") (pintype "bidirectional"))
      (node (ref "CON10") (pin "G1") (pinfunction "SHIELD_G1") (pintype "bidirectional"))
      (node (ref "CON10") (pin "G2") (pinfunction "SHEILD_G2") (pintype "bidirectional"))
      (node (ref "CON10") (pin "G3") (pinfunction "SHIELD_G3") (pintype "bidirectional"))
      (node (ref "CON11") (pin "3") (pinfunction "GND_3") (pintype "bidirectional"))
      (node (ref "CON11") (pin "5") (pinfunction "GND_5") (pintype "bidirectional"))
      (node (ref "CON11") (pin "9") (pinfunction "GND_9") (pintype "bidirectional"))
      (node (ref "CON12") (pin "3") (pinfunction "GND_3") (pintype "bidirectional"))
      (node (ref "CON2") (pin "4") (pinfunction "GND_4") (pintype "bidirectional"))
      (node (ref "CON3") (pin "4") (pinfunction "GND_4") (pintype "bidirectional"))
      (node (ref "CON4") (pin "4") (pinfunction "GND_4") (pintype "bidirectional"))
      (node (ref "CON5") (pin "4") (pinfunction "GND_4") (pintype "bidirectional"))
      (node (ref "CON6") (pin "4") (pinfunction "GND_4") (pintype "bidirectional"))
      (node (ref "CON8") (pin "4") (pinfunction "GND_4") (pintype "bidirectional"))
      (node (ref "CON9") (pin "GND") (pinfunction "GND_GND") (pintype "bidirectional"))
      (node (ref "IC1") (pin "2") (pinfunction "GND_2") (pintype "bidirectional"))
      (node (ref "IC2") (pin "1") (pinfunction "GND_1") (pintype "input"))
      (node (ref "IC3") (pin "33") (pinfunction "VSS_33") (pintype "passive"))
      (node (ref "IC4") (pin "4") (pinfunction "GND_4") (pintype "bidirectional"))
      (node (ref "IC4") (pin "5") (pinfunction "A2_5") (pintype "bidirectional"))
      (node (ref "IC4") (pin "6") (pinfunction "A1_6") (pintype "bidirectional"))
      (node (ref "IC4") (pin "7") (pinfunction "A0_7") (pintype "bidirectional"))
      (node (ref "IC5") (pin "1") (pinfunction "A0_1") (pintype "bidirectional"))
      (node (ref "IC5") (pin "2") (pinfunction "A1_2") (pintype "bidirectional"))
      (node (ref "IC5") (pin "3") (pinfunction "A2_3") (pintype "bidirectional"))
      (node (ref "IC5") (pin "4") (pinfunction "VSS_4") (pintype "power_in"))
      (node (ref "JP3") (pin "1") (pinfunction "1_1") (pintype "passive"))
      (node (ref "LCD1") (pin "K") (pinfunction "K_K") (pintype "bidirectional"))
      (node (ref "LCD1") (pin "P$11") (pinfunction "VSS_P$11") (pintype "bidirectional"))
      (node (ref "R16") (pin "2") (pinfunction "P$2_2") (pintype "passive"))
      (node (ref "R28") (pin "2") (pinfunction "P$2_2") (pintype "passive"))
      (node (ref "R3") (pin "1") (pinfunction "P$1_1") (pintype "passive"))
      (node (ref "SW1") (pin "B1") (pinfunction "B1_B1") (pintype "passive"))
      (node (ref "SW1") (pin "B2") (pinfunction "B2_B2") (pintype "passive"))
      (node (ref "T2") (pin "2") (pinfunction "E_2") (pintype "passive"))
      (node (ref "TP12") (pin "TP") (pinfunction "TP_TP") (pintype "input"))
      (node (ref "TP13") (pin "TP") (pinfunction "TP_TP") (pintype "input"))
      (node (ref "TP14") (pin "TP") (pinfunction "TP_TP") (pintype "input"))
      (node (ref "TP15") (pin "TP") (pinfunction "TP_TP") (pintype "input"))
      (node (ref "TP2") (pin "TP") (pinfunction "TP_TP") (pintype "input"))
      (node (ref "VR1") (pin "P$1") (pinfunction "A_P$1") (pintype "passive"))
    )
    (net (code "9") (name "GP0") (class "Default")
      (node (ref "R16") (pin "1") (pinfunction "P$1_1") (pintype "passive"))
      (node (ref "SKT1") (pin "16") (pinfunction "GP0_16") (pintype "bidirectional"))
      (node (ref "SKT1") (pin "P$56") (pinfunction "P$56_P$56") (pintype "bidirectional"))
      (node (ref "SW2") (pin "A1") (pinfunction "A1_A1") (pintype "passive"))
      (node (ref "SW2") (pin "A2") (pinfunction "A2_A2") (pintype "passive"))
    )
    (net (code "10") (name "GP1") (class "Default")
      (node (ref "CON1") (pin "4") (pinfunction "SEL_4") (pintype "bidirectional"))
      (node (ref "SKT1") (pin "17") (pinfunction "GP1_17") (pintype "bidirectional"))
      (node (ref "SKT1") (pin "P$57") (pinfunction "P$57_P$57") (pintype "bidirectional"))
    )
    (net (code "11") (name "GP2") (class "Default")
      (node (ref "CON10") (pin "2") (pinfunction "NCS_2") (pintype "bidirectional"))
      (node (ref "CON4") (pin "1") (pinfunction "A/D0_1") (pintype "bidirectional"))
      (node (ref "R24") (pin "2") (pinfunction "P$2_2") (pintype "passive"))
      (node (ref "SKT1") (pin "24") (pinfunction "GP2_24") (pintype "bidirectional"))
      (node (ref "SKT1") (pin "P$64") (pinfunction "P$64_P$64") (pintype "bidirectional"))
    )
    (net (code "12") (name "GP3") (class "Default")
      (node (ref "CON4") (pin "2") (pinfunction "A/D1_2") (pintype "bidirectional"))
      (node (ref "R24") (pin "1") (pinfunction "P$1_1") (pintype "passive"))
      (node (ref "SKT1") (pin "25") (pinfunction "GP3_25") (pintype "bidirectional"))
      (node (ref "SKT1") (pin "P$65") (pinfunction "P$65_P$65") (pintype "bidirectional"))
    )
    (net (code "13") (name "GP4") (class "Default")
      (node (ref "CON7") (pin "4") (pinfunction "SEL_4") (pintype "bidirectional"))
      (node (ref "SKT1") (pin "33") (pinfunction "GP4_33") (pintype "bidirectional"))
      (node (ref "SKT1") (pin "P$73") (pinfunction "P$73_P$73") (pintype "bidirectional"))
    )
    (net (code "14") (name "GP5") (class "Default")
      (node (ref "LCD1") (pin "P$15") (pinfunction "A0_P$15") (pintype "bidirectional"))
      (node (ref "SKT1") (pin "34") (pinfunction "GP5_34") (pintype "bidirectional"))
      (node (ref "SKT1") (pin "P$74") (pinfunction "P$74_P$74") (pintype "bidirectional"))
    )
    (net (code "15") (name "GP6") (class "Default")
      (node (ref "LCD1") (pin "P$16") (pinfunction "RST_P$16") (pintype "bidirectional"))
      (node (ref "SKT1") (pin "35") (pinfunction "GP6_35") (pintype "bidirectional"))
      (node (ref "SKT1") (pin "P$75") (pinfunction "P$75_P$75") (pintype "bidirectional"))
    )
    (net (code "16") (name "GP7") (class "Default")
      (node (ref "LCD1") (pin "P$17") (pinfunction "CS1B_P$17") (pintype "bidirectional"))
      (node (ref "SKT1") (pin "36") (pinfunction "GP7_36") (pintype "bidirectional"))
      (node (ref "SKT1") (pin "P$76") (pinfunction "P$76_P$76") (pintype "bidirectional"))
    )
    (net (code "17") (name "GP8") (class "Default")
      (node (ref "SKT1") (pin "37") (pinfunction "GP8_37") (pintype "bidirectional"))
      (node (ref "SKT1") (pin "P$77") (pinfunction "P$77_P$77") (pintype "bidirectional"))
    )
    (net (code "18") (name "IF_NRESET") (class "Default")
      (node (ref "C4") (pin "1") (pinfunction "P$1_1") (pintype "passive"))
      (node (ref "IC3") (pin "2") (pinfunction "~{RESET}/PIO0_0_2") (pintype "bidirectional"))
      (node (ref "R5") (pin "1") (pinfunction "P$1_1") (pintype "passive"))
    )
    (net (code "19") (name "IF_SCL") (class "Default")
      (node (ref "IC3") (pin "10") (pinfunction "PIO0_4/SCL_10") (pintype "bidirectional"))
      (node (ref "TP4") (pin "TP") (pinfunction "TP_TP") (pintype "input"))
    )
    (net (code "20") (name "IF_SDA") (class "Default")
      (node (ref "IC3") (pin "11") (pinfunction "PIO0_5/SDA_11") (pintype "bidirectional"))
      (node (ref "TP5") (pin "TP") (pinfunction "TP_TP") (pintype "input"))
    )
    (net (code "21") (name "IF_SWCLK") (class "Default")
      (node (ref "IC3") (pin "19") (pinfunction "SWCLK/PIO0_10/SCK0/CT16B0_MAT2_19") (pintype "bidirectional"))
      (node (ref "TP10") (pin "TP") (pinfunction "TP_TP") (pintype "input"))
    )
    (net (code "22") (name "IF_SWDIO") (class "Default")
      (node (ref "IC3") (pin "25") (pinfunction "SWDIO/PIO0_15/AD4/CT32B1_MAT2_25") (pintype "bidirectional"))
      (node (ref "TP9") (pin "TP") (pinfunction "TP_TP") (pintype "input"))
    )
    (net (code "23") (name "LED_COM_GREEN") (class "Default")
      (node (ref "IC3") (pin "21") (pinfunction "TDI/PIO0_11/AD0/CT32B0_MAT3_21") (pintype "bidirectional"))
      (node (ref "LED2") (pin "C") (pinfunction "C_C") (pintype "passive"))
    )
    (net (code "24") (name "LED_DAP_BLUE") (class "Default")
      (node (ref "IC3") (pin "12") (pinfunction "PIO0_21/CT16B1_MAT0_12") (pintype "bidirectional"))
      (node (ref "LED1") (pin "C") (pinfunction "C_C") (pintype "passive"))
    )
    (net (code "25") (name "LED_PWR_RED") (class "Default")
      (node (ref "IC3") (pin "7") (pinfunction "PIO0_20/CT16B1_CAP0_7") (pintype "bidirectional"))
      (node (ref "LED3") (pin "A") (pinfunction "A_A") (pintype "passive"))
    )
    (net (code "26") (name "MISO1") (class "Default")
      (node (ref "CON1") (pin "2") (pinfunction "MISO_2") (pintype "bidirectional"))
      (node (ref "CON10") (pin "7") (pinfunction "MISO_7") (pintype "bidirectional"))
      (node (ref "SKT1") (pin "14") (pinfunction "MISO1_14") (pintype "bidirectional"))
      (node (ref "SKT1") (pin "P$54") (pinfunction "P$54_P$54") (pintype "bidirectional"))
    )
    (net (code "27") (name "MISO2") (class "Default")
      (node (ref "CON7") (pin "2") (pinfunction "MISO_2") (pintype "bidirectional"))
      (node (ref "SKT1") (pin "27") (pinfunction "MISO2_27") (pintype "bidirectional"))
      (node (ref "SKT1") (pin "P$67") (pinfunction "P$67_P$67") (pintype "bidirectional"))
    )
    (net (code "28") (name "MODULE_GND") (class "Default")
      (node (ref "R28") (pin "1") (pinfunction "P$1_1") (pintype "passive"))
      (node (ref "SKT1") (pin "1") (pinfunction "GND_1") (pintype "bidirectional"))
      (node (ref "SKT1") (pin "40") (pinfunction "GND_40") (pintype "bidirectional"))
      (node (ref "SKT1") (pin "P$41") (pinfunction "P$41_P$41") (pintype "bidirectional"))
      (node (ref "SKT1") (pin "P$80") (pinfunction "P$80_P$80") (pintype "bidirectional"))
      (node (ref "T2") (pin "3") (pinfunction "C_3") (pintype "passive"))
    )
    (net (code "29") (name "MOSI1") (class "Default")
      (node (ref "CON1") (pin "3") (pinfunction "MOSI_3") (pintype "bidirectional"))
      (node (ref "CON10") (pin "3") (pinfunction "MOSI_3") (pintype "bidirectional"))
      (node (ref "LCD1") (pin "P$13") (pinfunction "SDA_P$13") (pintype "bidirectional"))
      (node (ref "SKT1") (pin "13") (pinfunction "MOSI1_13") (pintype "bidirectional"))
      (node (ref "SKT1") (pin "P$53") (pinfunction "P$53_P$53") (pintype "bidirectional"))
    )
    (net (code "30") (name "MOSI2") (class "Default")
      (node (ref "CON7") (pin "3") (pinfunction "MOSI_3") (pintype "bidirectional"))
      (node (ref "SKT1") (pin "28") (pinfunction "MOSI2_28") (pintype "bidirectional"))
      (node (ref "SKT1") (pin "P$68") (pinfunction "P$68_P$68") (pintype "bidirectional"))
    )
    (net (code "31") (name "Net-(C6-P$1)") (class "Default")
      (node (ref "C6") (pin "1") (pinfunction "P$1_1") (pintype "passive"))
      (node (ref "IC3") (pin "5") (pinfunction "XTALOUT_5") (pintype "output"))
      (node (ref "Q1") (pin "P$1") (pinfunction "1_P$1") (pintype "passive"))
    )
    (net (code "32") (name "Net-(C7-P$1)") (class "Default")
      (node (ref "C7") (pin "1") (pinfunction "P$1_1") (pintype "passive"))
      (node (ref "IC3") (pin "4") (pinfunction "XTALIN_4") (pintype "input"))
      (node (ref "Q1") (pin "P$3") (pinfunction "2_P$3") (pintype "passive"))
    )
    (net (code "33") (name "Net-(C8-P$1)") (class "Default")
      (node (ref "C8") (pin "1") (pinfunction "P$1_1") (pintype "passive"))
      (node (ref "IC3") (pin "13") (pinfunction "USB_DM_13") (pintype "bidirectional"))
      (node (ref "R9") (pin "2") (pinfunction "P$2_2") (pintype "passive"))
    )
    (net (code "34") (name "Net-(C9-P$1)") (class "Default")
      (node (ref "C9") (pin "1") (pinfunction "P$1_1") (pintype "passive"))
      (node (ref "IC3") (pin "14") (pinfunction "USB_DP_14") (pintype "bidirectional"))
      (node (ref "R10") (pin "2") (pinfunction "P$2_2") (pintype "passive"))
      (node (ref "R8") (pin "2") (pinfunction "P$2_2") (pintype "passive"))
    )
    (net (code "35") (name "Net-(C11-P$1)") (class "Default")
      (node (ref "C11") (pin "1") (pinfunction "P$1_1") (pintype "passive"))
      (node (ref "LCD1") (pin "P$1") (pinfunction "V0_P$1") (pintype "bidirectional"))
    )
    (net (code "36") (name "Net-(C12-P$1)") (class "Default")
      (node (ref "C12") (pin "1") (pinfunction "P$1_1") (pintype "passive"))
      (node (ref "LCD1") (pin "P$2") (pinfunction "V1_P$2") (pintype "bidirectional"))
    )
    (net (code "37") (name "Net-(C13-P$1)") (class "Default")
      (node (ref "C13") (pin "1") (pinfunction "P$1_1") (pintype "passive"))
      (node (ref "LCD1") (pin "P$3") (pinfunction "V2_P$3") (pintype "bidirectional"))
    )
    (net (code "38") (name "Net-(C14-P$1)") (class "Default")
      (node (ref "C14") (pin "1") (pinfunction "P$1_1") (pintype "passive"))
      (node (ref "LCD1") (pin "P$4") (pinfunction "V3_P$4") (pintype "bidirectional"))
    )
    (net (code "39") (name "Net-(C15-P$1)") (class "Default")
      (node (ref "C15") (pin "1") (pinfunction "P$1_1") (pintype "passive"))
      (node (ref "LCD1") (pin "P$5") (pinfunction "V4_P$5") (pintype "bidirectional"))
    )
    (net (code "40") (name "Net-(C16-P$1)") (class "Default")
      (node (ref "C16") (pin "1") (pinfunction "P$1_1") (pintype "passive"))
      (node (ref "LCD1") (pin "P$9") (pinfunction "C1-_P$9") (pintype "bidirectional"))
    )
    (net (code "41") (name "Net-(C16-P$2)") (class "Default")
      (node (ref "C16") (pin "2") (pinfunction "P$2_2") (pintype "passive"))
      (node (ref "LCD1") (pin "P$8") (pinfunction "C1+_P$8") (pintype "bidirectional"))
    )
    (net (code "42") (name "Net-(C17-P$1)") (class "Default")
      (node (ref "C17") (pin "1") (pinfunction "P$1_1") (pintype "passive"))
      (node (ref "LCD1") (pin "P$7") (pinfunction "C2+_P$7") (pintype "bidirectional"))
    )
    (net (code "43") (name "Net-(C17-P$2)") (class "Default")
      (node (ref "C17") (pin "2") (pinfunction "P$2_2") (pintype "passive"))
      (node (ref "LCD1") (pin "P$6") (pinfunction "C2-_P$6") (pintype "bidirectional"))
    )
    (net (code "44") (name "Net-(C18-P$1)") (class "Default")
      (node (ref "C18") (pin "1") (pinfunction "P$1_1") (pintype "passive"))
      (node (ref "LCD1") (pin "P$10") (pinfunction "VOUT_P$10") (pintype "bidirectional"))
    )
    (net (code "45") (name "Net-(CON9-PadD+)") (class "Default")
      (node (ref "CON9") (pin "D+") (pinfunction "D+_D+") (pintype "bidirectional"))
      (node (ref "IC1") (pin "1") (pinfunction "IO1_1") (pintype "bidirectional"))
    )
    (net (code "46") (name "Net-(CON9-PadD-)") (class "Default")
      (node (ref "CON9") (pin "D-") (pinfunction "D-_D-") (pintype "bidirectional"))
      (node (ref "IC1") (pin "3") (pinfunction "IO2_3") (pintype "bidirectional"))
    )
    (net (code "47") (name "Net-(CON12-PWR-Pad1-1)") (class "Default")
      (node (ref "CON12") (pin "1-1") (pinfunction "PWR_1-1") (pintype "bidirectional"))
      (node (ref "CON12") (pin "1-2") (pinfunction "PWR_1-2") (pintype "bidirectional"))
      (node (ref "D2") (pin "A") (pinfunction "A_A") (pintype "passive"))
    )
    (net (code "48") (name "Net-(IC1-VBUS)") (class "Default")
      (node (ref "CON9") (pin "VBUS") (pinfunction "VBUS_VBUS") (pintype "bidirectional"))
      (node (ref "D3") (pin "A") (pinfunction "A_A") (pintype "passive"))
      (node (ref "IC1") (pin "5") (pinfunction "VBUS_5") (pintype "bidirectional"))
    )
    (net (code "49") (name "Net-(IC2-IN)") (class "Default")
      (node (ref "IC2") (pin "3") (pinfunction "IN_3") (pintype "input"))
      (node (ref "SW3") (pin "3") (pinfunction "3_3") (pintype "bidirectional"))
    )
    (net (code "50") (name "Net-(IC3-PIO0_3{slash}USB_VBUS)") (class "Default")
      (node (ref "IC3") (pin "9") (pinfunction "PIO0_3/USB_VBUS_9") (pintype "bidirectional"))
      (node (ref "R4") (pin "1") (pinfunction "P$1_1") (pintype "passive"))
    )
    (net (code "51") (name "Net-(R1-P$2)") (class "Default")
      (node (ref "LED1") (pin "A") (pinfunction "A_A") (pintype "passive"))
      (node (ref "R1") (pin "2") (pinfunction "P$2_2") (pintype "passive"))
    )
    (net (code "52") (name "Net-(R2-P$2)") (class "Default")
      (node (ref "LED2") (pin "A") (pinfunction "A_A") (pintype "passive"))
      (node (ref "R2") (pin "2") (pinfunction "P$2_2") (pintype "passive"))
    )
    (net (code "53") (name "Net-(R3-P$2)") (class "Default")
      (node (ref "LED3") (pin "C") (pinfunction "C_C") (pintype "passive"))
      (node (ref "R3") (pin "2") (pinfunction "P$2_2") (pintype "passive"))
    )
    (net (code "54") (name "Net-(R8-P$1)") (class "Default")
      (node (ref "R8") (pin "1") (pinfunction "P$1_1") (pintype "passive"))
      (node (ref "T1") (pin "3") (pinfunction "D_3") (pintype "passive"))
    )
    (net (code "55") (name "Net-(R11-P$2)") (class "Default")
      (node (ref "LED4") (pin "C") (pinfunction "C_C") (pintype "passive"))
      (node (ref "R11") (pin "2") (pinfunction "P$2_2") (pintype "passive"))
    )
    (net (code "56") (name "Net-(R12-P$2)") (class "Default")
      (node (ref "LED5") (pin "C") (pinfunction "C_C") (pintype "passive"))
      (node (ref "R12") (pin "2") (pinfunction "P$2_2") (pintype "passive"))
    )
    (net (code "57") (name "Net-(R13-P$2)") (class "Default")
      (node (ref "LED6") (pin "C") (pinfunction "C_C") (pintype "passive"))
      (node (ref "R13") (pin "2") (pinfunction "P$2_2") (pintype "passive"))
    )
    (net (code "58") (name "Net-(R17-P$2)") (class "Default")
      (node (ref "LCD1") (pin "A") (pinfunction "A_A") (pintype "bidirectional"))
      (node (ref "R17") (pin "2") (pinfunction "P$2_2") (pintype "passive"))
    )
    (net (code "59") (name "Net-(R19-P$2)") (class "Default")
      (node (ref "R19") (pin "2") (pinfunction "P$2_2") (pintype "passive"))
      (node (ref "R20") (pin "2") (pinfunction "P$2_2") (pintype "passive"))
      (node (ref "R21") (pin "2") (pinfunction "P$2_2") (pintype "passive"))
      (node (ref "TP3") (pin "TP") (pinfunction "TP_TP") (pintype "input"))
    )
    (net (code "60") (name "Net-(R22-P$1)") (class "Default")
      (node (ref "R22") (pin "1") (pinfunction "P$1_1") (pintype "passive"))
      (node (ref "VR1") (pin "P$2") (pinfunction "S_P$2") (pintype "passive"))
    )
    (net (code "61") (name "Net-(R26-P$1)") (class "Default")
      (node (ref "R26") (pin "1") (pinfunction "P$1_1") (pintype "passive"))
      (node (ref "T2") (pin "1") (pinfunction "B_1") (pintype "passive"))
    )
    (net (code "62") (name "Net-(R29-P$2)") (class "Default")
      (node (ref "JP3") (pin "2") (pinfunction "2_2") (pintype "passive"))
      (node (ref "R29") (pin "2") (pinfunction "P$2_2") (pintype "passive"))
      (node (ref "T3") (pin "B") (pinfunction "G_B") (pintype "passive"))
    )
    (net (code "63") (name "Net-(R30-P$2)") (class "Default")
      (node (ref "R30") (pin "2") (pinfunction "P$2_2") (pintype "passive"))
      (node (ref "SW3") (pin "2") (pinfunction "2_2") (pintype "bidirectional"))
      (node (ref "T3") (pin "C") (pinfunction "D_C") (pintype "passive"))
    )
    (net (code "64") (name "PIO0_14") (class "Default")
      (node (ref "IC3") (pin "24") (pinfunction "~{TRST}/PIO0_14/AD3/CT32B1_MAT1_24") (pintype "bidirectional"))
      (node (ref "TP11") (pin "TP") (pinfunction "TP_TP") (pintype "input"))
    )
    (net (code "65") (name "PWM0") (class "Default")
      (node (ref "R11") (pin "1") (pinfunction "P$1_1") (pintype "passive"))
      (node (ref "SKT1") (pin "21") (pinfunction "PWM0_21") (pintype "bidirectional"))
      (node (ref "SKT1") (pin "P$61") (pinfunction "P$61_P$61") (pintype "bidirectional"))
    )
    (net (code "66") (name "PWM1") (class "Default")
      (node (ref "R12") (pin "1") (pinfunction "P$1_1") (pintype "passive"))
      (node (ref "SKT1") (pin "22") (pinfunction "PWM1_22") (pintype "bidirectional"))
      (node (ref "SKT1") (pin "P$62") (pinfunction "P$62_P$62") (pintype "bidirectional"))
    )
    (net (code "67") (name "PWM2") (class "Default")
      (node (ref "R13") (pin "1") (pinfunction "P$1_1") (pintype "passive"))
      (node (ref "SKT1") (pin "23") (pinfunction "PWM2_23") (pintype "bidirectional"))
      (node (ref "SKT1") (pin "P$63") (pinfunction "P$63_P$63") (pintype "bidirectional"))
    )
    (net (code "68") (name "RX1") (class "Default")
      (node (ref "CON2") (pin "1") (pinfunction "RX/SCL_1") (pintype "bidirectional"))
      (node (ref "R23") (pin "2") (pinfunction "P$2_2") (pintype "passive"))
      (node (ref "SKT1") (pin "10") (pinfunction "RX1_10") (pintype "bidirectional"))
      (node (ref "SKT1") (pin "P$50") (pinfunction "P$50_P$50") (pintype "bidirectional"))
    )
    (net (code "69") (name "RX2") (class "Default")
      (node (ref "CON6") (pin "1") (pinfunction "RX/SCL_1") (pintype "bidirectional"))
      (node (ref "R18") (pin "2") (pinfunction "P$2_2") (pintype "passive"))
      (node (ref "SKT1") (pin "31") (pinfunction "RX2_31") (pintype "bidirectional"))
      (node (ref "SKT1") (pin "P$71") (pinfunction "P$71_P$71") (pintype "bidirectional"))
    )
    (net (code "70") (name "SCK1") (class "Default")
      (node (ref "CON1") (pin "1") (pinfunction "SCK_1") (pintype "bidirectional"))
      (node (ref "CON10") (pin "5") (pinfunction "SCK_5") (pintype "bidirectional"))
      (node (ref "LCD1") (pin "P$14") (pinfunction "SCL_P$14") (pintype "bidirectional"))
      (node (ref "SKT1") (pin "15") (pinfunction "SCK1_15") (pintype "bidirectional"))
      (node (ref "SKT1") (pin "P$55") (pinfunction "P$55_P$55") (pintype "bidirectional"))
    )
    (net (code "71") (name "SCK2") (class "Default")
      (node (ref "CON7") (pin "1") (pinfunction "SCK_1") (pintype "bidirectional"))
      (node (ref "SKT1") (pin "26") (pinfunction "SCK2_26") (pintype "bidirectional"))
      (node (ref "SKT1") (pin "P$66") (pinfunction "P$66_P$66") (pintype "bidirectional"))
    )
    (net (code "72") (name "SCL") (class "Default")
      (node (ref "IC4") (pin "2") (pinfunction "SCL_2") (pintype "bidirectional"))
      (node (ref "IC5") (pin "6") (pinfunction "SCL_6") (pintype "bidirectional"))
      (node (ref "JP4") (pin "4") (pinfunction "4_4") (pintype "passive"))
      (node (ref "R15") (pin "1") (pinfunction "P$1_1") (pintype "passive"))
    )
    (net (code "73") (name "SCL1") (class "Default")
      (node (ref "CON5") (pin "1") (pinfunction "RX/SCL_1") (pintype "bidirectional"))
      (node (ref "JP4") (pin "2") (pinfunction "2_2") (pintype "passive"))
      (node (ref "SKT1") (pin "12") (pinfunction "SCL1_12") (pintype "bidirectional"))
      (node (ref "SKT1") (pin "P$52") (pinfunction "P$52_P$52") (pintype "bidirectional"))
    )
    (net (code "74") (name "SCL2") (class "Default")
      (node (ref "CON8") (pin "1") (pinfunction "RX/SCL_1") (pintype "bidirectional"))
      (node (ref "JP4") (pin "6") (pinfunction "6_6") (pintype "passive"))
      (node (ref "SKT1") (pin "29") (pinfunction "SCL2_29") (pintype "bidirectional"))
      (node (ref "SKT1") (pin "P$69") (pinfunction "P$69_P$69") (pintype "bidirectional"))
    )
    (net (code "75") (name "SDA") (class "Default")
      (node (ref "IC4") (pin "1") (pinfunction "SDA_1") (pintype "bidirectional"))
      (node (ref "IC5") (pin "5") (pinfunction "SDA_5") (pintype "bidirectional"))
      (node (ref "JP4") (pin "3") (pinfunction "3_3") (pintype "passive"))
      (node (ref "R14") (pin "1") (pinfunction "P$1_1") (pintype "passive"))
    )
    (net (code "76") (name "SDA1") (class "Default")
      (node (ref "CON5") (pin "2") (pinfunction "TX/SDA_2") (pintype "bidirectional"))
      (node (ref "JP4") (pin "1") (pinfunction "1_1") (pintype "passive"))
      (node (ref "SKT1") (pin "11") (pinfunction "SDA1_11") (pintype "bidirectional"))
      (node (ref "SKT1") (pin "P$51") (pinfunction "P$51_P$51") (pintype "bidirectional"))
    )
    (net (code "77") (name "SDA2") (class "Default")
      (node (ref "CON8") (pin "2") (pinfunction "TX/SDA_2") (pintype "bidirectional"))
      (node (ref "JP4") (pin "5") (pinfunction "5_5") (pintype "passive"))
      (node (ref "SKT1") (pin "30") (pinfunction "SDA2_30") (pintype "bidirectional"))
      (node (ref "SKT1") (pin "P$70") (pinfunction "P$70_P$70") (pintype "bidirectional"))
    )
    (net (code "78") (name "TGT_CTS") (class "Default")
      (node (ref "IC3") (pin "30") (pinfunction "PIO0_17/~{RTS}/CT32B0_CAP0/SCLK_30") (pintype "bidirectional"))
      (node (ref "SKT1") (pin "39") (pinfunction "TGT_CTS_39") (pintype "bidirectional"))
      (node (ref "SKT1") (pin "P$79") (pinfunction "P$79_P$79") (pintype "bidirectional"))
    )
    (net (code "79") (name "TGT_NRESET") (class "Default")
      (node (ref "CON11") (pin "10") (pinfunction "NRESET_10") (pintype "bidirectional"))
      (node (ref "D1") (pin "A") (pinfunction "A_A") (pintype "passive"))
      (node (ref "IC3") (pin "8") (pinfunction "PIO0_2/SSEL0/CT16B0_CAP0_8") (pintype "bidirectional"))
      (node (ref "SKT1") (pin "6") (pinfunction "NRESET_6") (pintype "bidirectional"))
      (node (ref "SKT1") (pin "P$46") (pinfunction "P$46_P$46") (pintype "bidirectional"))
    )
    (net (code "80") (name "TGT_NRESET_BUTTON") (class "Default")
      (node (ref "D1") (pin "K") (pinfunction "K_K") (pintype "passive"))
      (node (ref "R6") (pin "2") (pinfunction "P$2_2") (pintype "passive"))
      (node (ref "R7") (pin "2") (pinfunction "P$2_2") (pintype "passive"))
      (node (ref "SW1") (pin "A1") (pinfunction "A1_A1") (pintype "passive"))
      (node (ref "SW1") (pin "A2") (pinfunction "A2_A2") (pintype "passive"))
    )
    (net (code "81") (name "TGT_NRESET_FB") (class "Default")
      (node (ref "IC3") (pin "3") (pinfunction "PIO0_1/CLKOUT/CT32B0_MAT2/USB_FTOGGLE_3") (pintype "bidirectional"))
      (node (ref "R6") (pin "1") (pinfunction "P$1_1") (pintype "passive"))
    )
    (net (code "82") (name "TGT_NRESET_FB_ISP") (class "Default")
      (node (ref "IC3") (pin "1") (pinfunction "PIO1_19/~{DTR}/SSEL1_1") (pintype "bidirectional"))
      (node (ref "R7") (pin "1") (pinfunction "P$1_1") (pintype "passive"))
    )
    (net (code "83") (name "TGT_RTS") (class "Default")
      (node (ref "IC3") (pin "16") (pinfunction "PIO0_7/~{CTS}_16") (pintype "bidirectional"))
      (node (ref "JP2") (pin "2") (pinfunction "2_2") (pintype "passive"))
      (node (ref "SKT1") (pin "38") (pinfunction "TGT_RTS_38") (pintype "bidirectional"))
      (node (ref "SKT1") (pin "P$78") (pinfunction "P$78_P$78") (pintype "bidirectional"))
    )
    (net (code "84") (name "TGT_RX") (class "Default")
      (node (ref "CON11") (pin "8") (pinfunction "TGT_RX_8") (pintype "bidirectional"))
      (node (ref "IC3") (pin "32") (pinfunction "PIO0_19/TXD/CT32B0_MAT1_32") (pintype "bidirectional"))
      (node (ref "SKT1") (pin "8") (pinfunction "TGT_RX_8") (pintype "bidirectional"))
      (node (ref "SKT1") (pin "P$48") (pinfunction "P$48_P$48") (pintype "bidirectional"))
    )
    (net (code "85") (name "TGT_SWCLK") (class "Default")
      (node (ref "CON11") (pin "4") (pinfunction "SWCLK_4") (pintype "bidirectional"))
      (node (ref "IC3") (pin "18") (pinfunction "PIO0_9/MOSI0/CT16B0_MAT1_18") (pintype "bidirectional"))
      (node (ref "JP2") (pin "1") (pinfunction "1_1") (pintype "passive"))
      (node (ref "SKT1") (pin "5") (pinfunction "SWCLK_5") (pintype "bidirectional"))
      (node (ref "SKT1") (pin "P$45") (pinfunction "P$45_P$45") (pintype "bidirectional"))
    )
    (net (code "86") (name "TGT_SWDIO") (class "Default")
      (node (ref "CON11") (pin "2") (pinfunction "SWDIO_2") (pintype "bidirectional"))
      (node (ref "IC3") (pin "17") (pinfunction "PIO0_8/MISO0/CT16B0_MAT0_17") (pintype "bidirectional"))
      (node (ref "SKT1") (pin "4") (pinfunction "SWDIO_4") (pintype "bidirectional"))
      (node (ref "SKT1") (pin "P$44") (pinfunction "P$44_P$44") (pintype "bidirectional"))
    )
    (net (code "87") (name "TGT_TX") (class "Default")
      (node (ref "CON11") (pin "7") (pinfunction "TGT_TX_7") (pintype "bidirectional"))
      (node (ref "IC3") (pin "31") (pinfunction "PIO0_18/RXD/CT32B0_MAT0_31") (pintype "bidirectional"))
      (node (ref "SKT1") (pin "7") (pinfunction "TGT_TX_7") (pintype "bidirectional"))
      (node (ref "SKT1") (pin "P$47") (pinfunction "P$47_P$47") (pintype "bidirectional"))
    )
    (net (code "88") (name "TX1") (class "Default")
      (node (ref "CON2") (pin "2") (pinfunction "TX/SDA_2") (pintype "bidirectional"))
      (node (ref "R23") (pin "1") (pinfunction "P$1_1") (pintype "passive"))
      (node (ref "SKT1") (pin "9") (pinfunction "TX1_9") (pintype "bidirectional"))
      (node (ref "SKT1") (pin "P$49") (pinfunction "P$49_P$49") (pintype "bidirectional"))
    )
    (net (code "89") (name "TX2") (class "Default")
      (node (ref "CON6") (pin "2") (pinfunction "TX/SDA_2") (pintype "bidirectional"))
      (node (ref "R18") (pin "1") (pinfunction "P$1_1") (pintype "passive"))
      (node (ref "SKT1") (pin "32") (pinfunction "TX2_32") (pintype "bidirectional"))
      (node (ref "SKT1") (pin "P$72") (pinfunction "P$72_P$72") (pintype "bidirectional"))
    )
    (net (code "90") (name "USB-D+") (class "Default")
      (node (ref "IC1") (pin "6") (pinfunction "IO1_6") (pintype "bidirectional"))
      (node (ref "R10") (pin "1") (pinfunction "P$1_1") (pintype "passive"))
    )
    (net (code "91") (name "USB-D-") (class "Default")
      (node (ref "IC1") (pin "4") (pinfunction "IO2_4") (pintype "bidirectional"))
      (node (ref "R9") (pin "1") (pinfunction "P$1_1") (pintype "passive"))
    )
    (net (code "92") (name "USB-SCON") (class "Default")
      (node (ref "IC3") (pin "15") (pinfunction "PIO0_6/~{USB_CONNECT}/SCK0_15") (pintype "bidirectional"))
      (node (ref "T1") (pin "1") (pinfunction "G_1") (pintype "passive"))
    )
    (net (code "93") (name "VCC_GROVE") (class "Default")
      (node (ref "CON2") (pin "3") (pinfunction "VCC_3") (pintype "bidirectional"))
      (node (ref "CON3") (pin "3") (pinfunction "VCC_3") (pintype "bidirectional"))
      (node (ref "CON4") (pin "3") (pinfunction "VCC_3") (pintype "bidirectional"))
      (node (ref "CON5") (pin "3") (pinfunction "VCC_3") (pintype "bidirectional"))
      (node (ref "CON6") (pin "3") (pinfunction "VCC_3") (pintype "bidirectional"))
      (node (ref "CON8") (pin "3") (pinfunction "VCC_3") (pintype "bidirectional"))
      (node (ref "JP1") (pin "2") (pinfunction "2_2") (pintype "passive"))
    )
    (net (code "94") (name "V_ISENSE") (class "Default")
      (node (ref "CON11") (pin "1") (pinfunction "VCC_1") (pintype "bidirectional"))
      (node (ref "R25") (pin "1") (pinfunction "P$1_1") (pintype "passive"))
      (node (ref "SKT1") (pin "2") (pinfunction "3V3_2") (pintype "bidirectional"))
      (node (ref "SKT1") (pin "P$42") (pinfunction "P$42_P$42") (pintype "bidirectional"))
      (node (ref "TP8") (pin "TP") (pinfunction "TP_TP") (pintype "input"))
    )
    (net (code "95") (name "unconnected-(CON10-NC-Pad1)") (class "Default")
      (node (ref "CON10") (pin "1") (pinfunction "NC_1") (pintype "bidirectional"))
    )
    (net (code "96") (name "unconnected-(CON10-NC-Pad8)") (class "Default")
      (node (ref "CON10") (pin "8") (pinfunction "NC_8") (pintype "bidirectional"))
    )
    (net (code "97") (name "unconnected-(CON10-PadCD)") (class "Default")
      (node (ref "CON10") (pin "CD") (pinfunction "CD_CD") (pintype "bidirectional"))
    )
    (net (code "98") (name "unconnected-(CON11-SWO-Pad6)") (class "Default")
      (node (ref "CON11") (pin "6") (pinfunction "SWO_6") (pintype "bidirectional"))
    )
    (net (code "99") (name "unconnected-(CON12-GNDBREAK-Pad2)") (class "Default")
      (node (ref "CON12") (pin "2") (pinfunction "GNDBREAK_2") (pintype "bidirectional"))
    )
    (net (code "100") (name "unconnected-(IC3-PIO0_16{slash}AD5{slash}CT32B1_MAT3{slash}WAKEUP-Pad26)") (class "Default")
      (node (ref "IC3") (pin "26") (pinfunction "PIO0_16/AD5/CT32B1_MAT3/WAKEUP_26") (pintype "bidirectional"))
    )
    (net (code "101") (name "unconnected-(IC3-PIO1_15{slash}~{DCD}{slash}CT16B0_MAT2{slash}SCK1-Pad28)") (class "Default")
      (node (ref "IC3") (pin "28") (pinfunction "PIO1_15/~{DCD}/CT16B0_MAT2/SCK1_28") (pintype "bidirectional"))
    )
    (net (code "102") (name "unconnected-(IC3-TMS{slash}PIO0_12{slash}AD1{slash}CT32B1_CAP0-Pad22)") (class "Default")
      (node (ref "IC3") (pin "22") (pinfunction "TMS/PIO0_12/AD1/CT32B1_CAP0_22") (pintype "bidirectional"))
    )
    (net (code "103") (name "unconnected-(IC4-OS-Pad3)") (class "Default")
      (node (ref "IC4") (pin "3") (pinfunction "OS_3") (pintype "bidirectional"))
    )
    (net (code "104") (name "unconnected-(IC5-WP-Pad7)") (class "Default")
      (node (ref "IC5") (pin "7") (pinfunction "WP_7") (pintype "bidirectional"))
    )
    (net (code "105") (name "unconnected-(SW3-Pad1)") (class "Default")
      (node (ref "SW3") (pin "1") (pinfunction "1_1") (pintype "bidirectional"))
    )
    (net (code "106") (name "unconnected-(SW3-Pad5)") (class "Default")
      (node (ref "SW3") (pin "5") (pinfunction "5_5") (pintype "bidirectional"))
    )
    (net (code "107") (name "unconnected-(SW3-Pad6)") (class "Default")
      (node (ref "SW3") (pin "6") (pinfunction "6_6") (pintype "bidirectional"))
    )
    (net (code "108") (name "unconnected-(SW3-Pad7)") (class "Default")
      (node (ref "SW3") (pin "7") (pinfunction "7_7") (pintype "bidirectional"))
    )
    (net (code "109") (name "~{PWR_OFF}") (class "Default")
      (node (ref "IC3") (pin "23") (pinfunction "TDO/PIO0_13/AD2/CT32B1_MAT0_23") (pintype "bidirectional"))
      (node (ref "R26") (pin "2") (pinfunction "P$2_2") (pintype "passive"))
      (node (ref "R27") (pin "2") (pinfunction "P$2_2") (pintype "passive"))
    )
  )
)
